# VDAC2.net
KiCad netlist of a schematic drawn in EAGLE
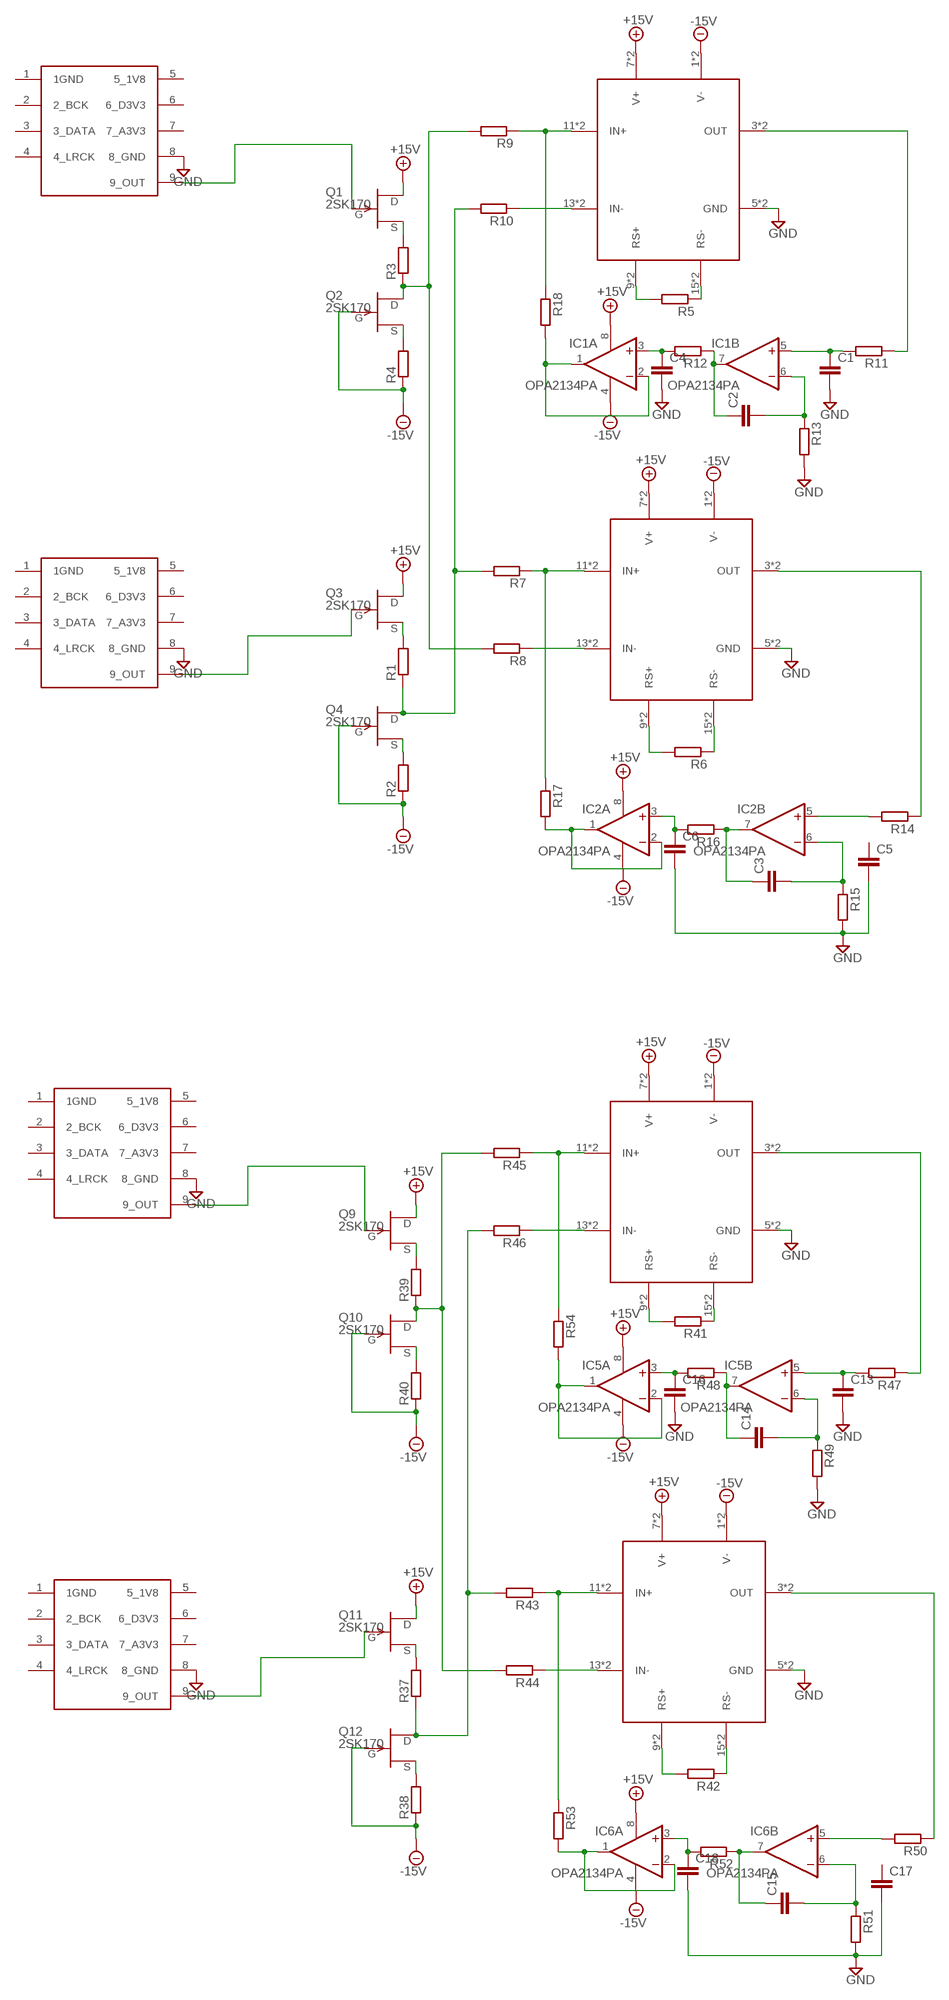
[diagram p0: schematic, sheet 1]

(export (version "E")
  (design (tool "Eeschema 10.0.6"))
  (components
    (comp (ref "C1")
      (value "C-EU050-050X075")
      (footprint "eagle-import:C050-050X075")
      (libsource (lib "eagle-import") (part "C-EU050-050X075"))
    )
    (comp (ref "C2")
      (value "C-EU050-035X075")
      (footprint "eagle-import:C050-035X075")
      (libsource (lib "eagle-import") (part "C-EU050-035X075"))
    )
    (comp (ref "C3")
      (value "C-EU050-035X075")
      (footprint "eagle-import:C050-035X075")
      (libsource (lib "eagle-import") (part "C-EU050-035X075"))
    )
    (comp (ref "C4")
      (value "C-EU050-035X075")
      (footprint "eagle-import:C050-035X075")
      (libsource (lib "eagle-import") (part "C-EU050-035X075"))
    )
    (comp (ref "C5")
      (value "C-EU050-050X075")
      (footprint "eagle-import:C050-050X075")
      (libsource (lib "eagle-import") (part "C-EU050-050X075"))
    )
    (comp (ref "C6")
      (value "C-EU050-035X075")
      (footprint "eagle-import:C050-035X075")
      (libsource (lib "eagle-import") (part "C-EU050-035X075"))
    )
    (comp (ref "C13")
      (value "C-EU050-050X075")
      (footprint "eagle-import:C050-050X075")
      (libsource (lib "eagle-import") (part "C-EU050-050X075"))
    )
    (comp (ref "C14")
      (value "C-EU050-035X075")
      (footprint "eagle-import:C050-035X075")
      (libsource (lib "eagle-import") (part "C-EU050-035X075"))
    )
    (comp (ref "C15")
      (value "C-EU050-035X075")
      (footprint "eagle-import:C050-035X075")
      (libsource (lib "eagle-import") (part "C-EU050-035X075"))
    )
    (comp (ref "C16")
      (value "C-EU050-035X075")
      (footprint "eagle-import:C050-035X075")
      (libsource (lib "eagle-import") (part "C-EU050-035X075"))
    )
    (comp (ref "C17")
      (value "C-EU050-050X075")
      (footprint "eagle-import:C050-050X075")
      (libsource (lib "eagle-import") (part "C-EU050-050X075"))
    )
    (comp (ref "C18")
      (value "C-EU050-035X075")
      (footprint "eagle-import:C050-035X075")
      (libsource (lib "eagle-import") (part "C-EU050-035X075"))
    )
    (comp (ref "IC1")
      (value "OPA2134PA")
      (footprint "eagle-import:DIL08")
      (libsource (lib "eagle-import") (part "OPA2PA134"))
    )
    (comp (ref "IC2")
      (value "OPA2134PA")
      (footprint "eagle-import:DIL08")
      (libsource (lib "eagle-import") (part "OPA2PA134"))
    )
    (comp (ref "IC5")
      (value "OPA2134PA")
      (footprint "eagle-import:DIL08")
      (libsource (lib "eagle-import") (part "OPA2PA134"))
    )
    (comp (ref "IC6")
      (value "OPA2134PA")
      (footprint "eagle-import:DIL08")
      (libsource (lib "eagle-import") (part "OPA2PA134"))
    )
    (comp (ref "Q1")
      (value "2SK170")
      (footprint "eagle-import:TO92-")
      (libsource (lib "eagle-import") (part "2SK170"))
    )
    (comp (ref "Q2")
      (value "2SK170")
      (footprint "eagle-import:TO92-")
      (libsource (lib "eagle-import") (part "2SK170"))
    )
    (comp (ref "Q3")
      (value "2SK170")
      (footprint "eagle-import:TO92-")
      (libsource (lib "eagle-import") (part "2SK170"))
    )
    (comp (ref "Q4")
      (value "2SK170")
      (footprint "eagle-import:TO92-")
      (libsource (lib "eagle-import") (part "2SK170"))
    )
    (comp (ref "Q9")
      (value "2SK170")
      (footprint "eagle-import:TO92-")
      (libsource (lib "eagle-import") (part "2SK170"))
    )
    (comp (ref "Q10")
      (value "2SK170")
      (footprint "eagle-import:TO92-")
      (libsource (lib "eagle-import") (part "2SK170"))
    )
    (comp (ref "Q11")
      (value "2SK170")
      (footprint "eagle-import:TO92-")
      (libsource (lib "eagle-import") (part "2SK170"))
    )
    (comp (ref "Q12")
      (value "2SK170")
      (footprint "eagle-import:TO92-")
      (libsource (lib "eagle-import") (part "2SK170"))
    )
    (comp (ref "R1")
      (value "R-EU_0309/10")
      (footprint "eagle-import:0309_10")
      (libsource (lib "eagle-import") (part "R-EU_0309/10"))
    )
    (comp (ref "R2")
      (value "R-EU_0309/10")
      (footprint "eagle-import:0309_10")
      (libsource (lib "eagle-import") (part "R-EU_0309/10"))
    )
    (comp (ref "R3")
      (value "R-EU_0309/10")
      (footprint "eagle-import:0309_10")
      (libsource (lib "eagle-import") (part "R-EU_0309/10"))
    )
    (comp (ref "R4")
      (value "R-EU_0309/10")
      (footprint "eagle-import:0309_10")
      (libsource (lib "eagle-import") (part "R-EU_0309/10"))
    )
    (comp (ref "R5")
      (value "R-EU_0309/10")
      (footprint "eagle-import:0309_10")
      (libsource (lib "eagle-import") (part "R-EU_0309/10"))
    )
    (comp (ref "R6")
      (value "R-EU_0309/10")
      (footprint "eagle-import:0309_10")
      (libsource (lib "eagle-import") (part "R-EU_0309/10"))
    )
    (comp (ref "R7")
      (value "R-EU_0309/10")
      (footprint "eagle-import:0309_10")
      (libsource (lib "eagle-import") (part "R-EU_0309/10"))
    )
    (comp (ref "R8")
      (value "R-EU_0309/10")
      (footprint "eagle-import:0309_10")
      (libsource (lib "eagle-import") (part "R-EU_0309/10"))
    )
    (comp (ref "R9")
      (value "R-EU_0309/10")
      (footprint "eagle-import:0309_10")
      (libsource (lib "eagle-import") (part "R-EU_0309/10"))
    )
    (comp (ref "R10")
      (value "R-EU_0309/10")
      (footprint "eagle-import:0309_10")
      (libsource (lib "eagle-import") (part "R-EU_0309/10"))
    )
    (comp (ref "R11")
      (value "R-EU_0309/10")
      (footprint "eagle-import:0309_10")
      (libsource (lib "eagle-import") (part "R-EU_0309/10"))
    )
    (comp (ref "R12")
      (value "R-EU_0309/10")
      (footprint "eagle-import:0309_10")
      (libsource (lib "eagle-import") (part "R-EU_0309/10"))
    )
    (comp (ref "R13")
      (value "R-EU_0309/10")
      (footprint "eagle-import:0309_10")
      (libsource (lib "eagle-import") (part "R-EU_0309/10"))
    )
    (comp (ref "R14")
      (value "R-EU_0309/10")
      (footprint "eagle-import:0309_10")
      (libsource (lib "eagle-import") (part "R-EU_0309/10"))
    )
    (comp (ref "R15")
      (value "R-EU_0309/10")
      (footprint "eagle-import:0309_10")
      (libsource (lib "eagle-import") (part "R-EU_0309/10"))
    )
    (comp (ref "R16")
      (value "R-EU_0309/10")
      (footprint "eagle-import:0309_10")
      (libsource (lib "eagle-import") (part "R-EU_0309/10"))
    )
    (comp (ref "R17")
      (value "R-EU_0309/10")
      (footprint "eagle-import:0309_10")
      (libsource (lib "eagle-import") (part "R-EU_0309/10"))
    )
    (comp (ref "R18")
      (value "R-EU_0309/10")
      (footprint "eagle-import:0309_10")
      (libsource (lib "eagle-import") (part "R-EU_0309/10"))
    )
    (comp (ref "R37")
      (value "R-EU_0309/10")
      (footprint "eagle-import:0309_10")
      (libsource (lib "eagle-import") (part "R-EU_0309/10"))
    )
    (comp (ref "R38")
      (value "R-EU_0309/10")
      (footprint "eagle-import:0309_10")
      (libsource (lib "eagle-import") (part "R-EU_0309/10"))
    )
    (comp (ref "R39")
      (value "R-EU_0309/10")
      (footprint "eagle-import:0309_10")
      (libsource (lib "eagle-import") (part "R-EU_0309/10"))
    )
    (comp (ref "R40")
      (value "R-EU_0309/10")
      (footprint "eagle-import:0309_10")
      (libsource (lib "eagle-import") (part "R-EU_0309/10"))
    )
    (comp (ref "R41")
      (value "R-EU_0309/10")
      (footprint "eagle-import:0309_10")
      (libsource (lib "eagle-import") (part "R-EU_0309/10"))
    )
    (comp (ref "R42")
      (value "R-EU_0309/10")
      (footprint "eagle-import:0309_10")
      (libsource (lib "eagle-import") (part "R-EU_0309/10"))
    )
    (comp (ref "R43")
      (value "R-EU_0309/10")
      (footprint "eagle-import:0309_10")
      (libsource (lib "eagle-import") (part "R-EU_0309/10"))
    )
    (comp (ref "R44")
      (value "R-EU_0309/10")
      (footprint "eagle-import:0309_10")
      (libsource (lib "eagle-import") (part "R-EU_0309/10"))
    )
    (comp (ref "R45")
      (value "R-EU_0309/10")
      (footprint "eagle-import:0309_10")
      (libsource (lib "eagle-import") (part "R-EU_0309/10"))
    )
    (comp (ref "R46")
      (value "R-EU_0309/10")
      (footprint "eagle-import:0309_10")
      (libsource (lib "eagle-import") (part "R-EU_0309/10"))
    )
    (comp (ref "R47")
      (value "R-EU_0309/10")
      (footprint "eagle-import:0309_10")
      (libsource (lib "eagle-import") (part "R-EU_0309/10"))
    )
    (comp (ref "R48")
      (value "R-EU_0309/10")
      (footprint "eagle-import:0309_10")
      (libsource (lib "eagle-import") (part "R-EU_0309/10"))
    )
    (comp (ref "R49")
      (value "R-EU_0309/10")
      (footprint "eagle-import:0309_10")
      (libsource (lib "eagle-import") (part "R-EU_0309/10"))
    )
    (comp (ref "R50")
      (value "R-EU_0309/10")
      (footprint "eagle-import:0309_10")
      (libsource (lib "eagle-import") (part "R-EU_0309/10"))
    )
    (comp (ref "R51")
      (value "R-EU_0309/10")
      (footprint "eagle-import:0309_10")
      (libsource (lib "eagle-import") (part "R-EU_0309/10"))
    )
    (comp (ref "R52")
      (value "R-EU_0309/10")
      (footprint "eagle-import:0309_10")
      (libsource (lib "eagle-import") (part "R-EU_0309/10"))
    )
    (comp (ref "R53")
      (value "R-EU_0309/10")
      (footprint "eagle-import:0309_10")
      (libsource (lib "eagle-import") (part "R-EU_0309/10"))
    )
    (comp (ref "R54")
      (value "R-EU_0309/10")
      (footprint "eagle-import:0309_10")
      (libsource (lib "eagle-import") (part "R-EU_0309/10"))
    )
    (comp (ref "U$1")
      (value "7130MOD")
      (footprint "eagle-import:7130MOD")
      (libsource (lib "eagle-import") (part "7130MOD"))
    )
    (comp (ref "U$2")
      (value "7130MOD")
      (footprint "eagle-import:7130MOD")
      (libsource (lib "eagle-import") (part "7130MOD"))
    )
    (comp (ref "U$5")
      (value "R2R")
      (footprint "eagle-import:R2R")
      (libsource (lib "eagle-import") (part "R2R"))
    )
    (comp (ref "U$6")
      (value "R2R")
      (footprint "eagle-import:R2R")
      (libsource (lib "eagle-import") (part "R2R"))
    )
    (comp (ref "U$9")
      (value "R2R")
      (footprint "eagle-import:R2R")
      (libsource (lib "eagle-import") (part "R2R"))
    )
    (comp (ref "U$10")
      (value "R2R")
      (footprint "eagle-import:R2R")
      (libsource (lib "eagle-import") (part "R2R"))
    )
    (comp (ref "U$11")
      (value "7130MOD")
      (footprint "eagle-import:7130MOD")
      (libsource (lib "eagle-import") (part "7130MOD"))
    )
    (comp (ref "U$12")
      (value "7130MOD")
      (footprint "eagle-import:7130MOD")
      (libsource (lib "eagle-import") (part "7130MOD"))
    )
  )
  (nets
    (net (code "1") (name "+15V") (class "Default")
      (node (ref "IC1") (pin "8") (pinfunction "V+_8") (pintype "power_in"))
      (node (ref "IC2") (pin "8") (pinfunction "V+_8") (pintype "power_in"))
      (node (ref "IC5") (pin "8") (pinfunction "V+_8") (pintype "power_in"))
      (node (ref "IC6") (pin "8") (pinfunction "V+_8") (pintype "power_in"))
      (node (ref "Q1") (pin "1") (pinfunction "D_1") (pintype "passive"))
      (node (ref "Q11") (pin "1") (pinfunction "D_1") (pintype "passive"))
      (node (ref "Q3") (pin "1") (pinfunction "D_1") (pintype "passive"))
      (node (ref "Q9") (pin "1") (pinfunction "D_1") (pintype "passive"))
      (node (ref "U$1") (pin "7") (pinfunction "V+_7") (pintype "bidirectional"))
      (node (ref "U$1") (pin "8") (pinfunction "V+_8") (pintype "bidirectional"))
      (node (ref "U$11") (pin "7") (pinfunction "V+_7") (pintype "bidirectional"))
      (node (ref "U$11") (pin "8") (pinfunction "V+_8") (pintype "bidirectional"))
      (node (ref "U$12") (pin "7") (pinfunction "V+_7") (pintype "bidirectional"))
      (node (ref "U$12") (pin "8") (pinfunction "V+_8") (pintype "bidirectional"))
      (node (ref "U$2") (pin "7") (pinfunction "V+_7") (pintype "bidirectional"))
      (node (ref "U$2") (pin "8") (pinfunction "V+_8") (pintype "bidirectional"))
    )
    (net (code "2") (name "-15V") (class "Default")
      (node (ref "IC1") (pin "4") (pinfunction "V-_4") (pintype "power_in"))
      (node (ref "IC2") (pin "4") (pinfunction "V-_4") (pintype "power_in"))
      (node (ref "IC5") (pin "4") (pinfunction "V-_4") (pintype "power_in"))
      (node (ref "IC6") (pin "4") (pinfunction "V-_4") (pintype "power_in"))
      (node (ref "Q10") (pin "2") (pinfunction "G_2") (pintype "passive"))
      (node (ref "Q12") (pin "2") (pinfunction "G_2") (pintype "passive"))
      (node (ref "Q2") (pin "2") (pinfunction "G_2") (pintype "passive"))
      (node (ref "Q4") (pin "2") (pinfunction "G_2") (pintype "passive"))
      (node (ref "R2") (pin "1") (pinfunction "1_1") (pintype "passive"))
      (node (ref "R38") (pin "1") (pinfunction "1_1") (pintype "passive"))
      (node (ref "R4") (pin "1") (pinfunction "1_1") (pintype "passive"))
      (node (ref "R40") (pin "1") (pinfunction "1_1") (pintype "passive"))
      (node (ref "U$1") (pin "1") (pinfunction "V-_1") (pintype "bidirectional"))
      (node (ref "U$1") (pin "2") (pinfunction "V-_2") (pintype "bidirectional"))
      (node (ref "U$11") (pin "1") (pinfunction "V-_1") (pintype "bidirectional"))
      (node (ref "U$11") (pin "2") (pinfunction "V-_2") (pintype "bidirectional"))
      (node (ref "U$12") (pin "1") (pinfunction "V-_1") (pintype "bidirectional"))
      (node (ref "U$12") (pin "2") (pinfunction "V-_2") (pintype "bidirectional"))
      (node (ref "U$2") (pin "1") (pinfunction "V-_1") (pintype "bidirectional"))
      (node (ref "U$2") (pin "2") (pinfunction "V-_2") (pintype "bidirectional"))
    )
    (net (code "3") (name "GND") (class "Default")
      (node (ref "C1") (pin "2") (pinfunction "2_2") (pintype "passive"))
      (node (ref "C13") (pin "2") (pinfunction "2_2") (pintype "passive"))
      (node (ref "C16") (pin "2") (pinfunction "2_2") (pintype "passive"))
      (node (ref "C17") (pin "2") (pinfunction "2_2") (pintype "passive"))
      (node (ref "C18") (pin "2") (pinfunction "2_2") (pintype "passive"))
      (node (ref "C4") (pin "2") (pinfunction "2_2") (pintype "passive"))
      (node (ref "C5") (pin "2") (pinfunction "2_2") (pintype "passive"))
      (node (ref "C6") (pin "2") (pinfunction "2_2") (pintype "passive"))
      (node (ref "R13") (pin "2") (pinfunction "2_2") (pintype "passive"))
      (node (ref "R15") (pin "2") (pinfunction "2_2") (pintype "passive"))
      (node (ref "R49") (pin "2") (pinfunction "2_2") (pintype "passive"))
      (node (ref "R51") (pin "2") (pinfunction "2_2") (pintype "passive"))
      (node (ref "U$1") (pin "5") (pinfunction "GND_5") (pintype "bidirectional"))
      (node (ref "U$1") (pin "6") (pinfunction "GND_6") (pintype "bidirectional"))
      (node (ref "U$10") (pin "8") (pinfunction "8_GND_8") (pintype "bidirectional"))
      (node (ref "U$11") (pin "5") (pinfunction "GND_5") (pintype "bidirectional"))
      (node (ref "U$11") (pin "6") (pinfunction "GND_6") (pintype "bidirectional"))
      (node (ref "U$12") (pin "5") (pinfunction "GND_5") (pintype "bidirectional"))
      (node (ref "U$12") (pin "6") (pinfunction "GND_6") (pintype "bidirectional"))
      (node (ref "U$2") (pin "5") (pinfunction "GND_5") (pintype "bidirectional"))
      (node (ref "U$2") (pin "6") (pinfunction "GND_6") (pintype "bidirectional"))
      (node (ref "U$5") (pin "8") (pinfunction "8_GND_8") (pintype "bidirectional"))
      (node (ref "U$6") (pin "8") (pinfunction "8_GND_8") (pintype "bidirectional"))
      (node (ref "U$9") (pin "8") (pinfunction "8_GND_8") (pintype "bidirectional"))
    )
    (net (code "4") (name "Net-(IC1A-+IN)") (class "Default")
      (node (ref "C4") (pin "1") (pinfunction "1_1") (pintype "passive"))
      (node (ref "IC1") (pin "3") (pinfunction "+IN_3") (pintype "input"))
      (node (ref "R12") (pin "2") (pinfunction "2_2") (pintype "passive"))
    )
    (net (code "5") (name "Net-(IC1A--IN)") (class "Default")
      (node (ref "IC1") (pin "1") (pinfunction "OUT_1") (pintype "output"))
      (node (ref "IC1") (pin "2") (pinfunction "-IN_2") (pintype "input"))
      (node (ref "R18") (pin "2") (pinfunction "2_2") (pintype "passive"))
    )
    (net (code "6") (name "Net-(IC1B-+IN)") (class "Default")
      (node (ref "C1") (pin "1") (pinfunction "1_1") (pintype "passive"))
      (node (ref "IC1") (pin "5") (pinfunction "+IN_5") (pintype "input"))
      (node (ref "R11") (pin "2") (pinfunction "2_2") (pintype "passive"))
    )
    (net (code "7") (name "Net-(IC1B--IN)") (class "Default")
      (node (ref "C2") (pin "2") (pinfunction "2_2") (pintype "passive"))
      (node (ref "IC1") (pin "6") (pinfunction "-IN_6") (pintype "input"))
      (node (ref "R13") (pin "1") (pinfunction "1_1") (pintype "passive"))
    )
    (net (code "8") (name "Net-(IC1B-OUT)") (class "Default")
      (node (ref "C2") (pin "1") (pinfunction "1_1") (pintype "passive"))
      (node (ref "IC1") (pin "7") (pinfunction "OUT_7") (pintype "output"))
      (node (ref "R12") (pin "1") (pinfunction "1_1") (pintype "passive"))
    )
    (net (code "9") (name "Net-(IC2A-+IN)") (class "Default")
      (node (ref "C6") (pin "1") (pinfunction "1_1") (pintype "passive"))
      (node (ref "IC2") (pin "3") (pinfunction "+IN_3") (pintype "input"))
      (node (ref "R16") (pin "2") (pinfunction "2_2") (pintype "passive"))
    )
    (net (code "10") (name "Net-(IC2A--IN)") (class "Default")
      (node (ref "IC2") (pin "1") (pinfunction "OUT_1") (pintype "output"))
      (node (ref "IC2") (pin "2") (pinfunction "-IN_2") (pintype "input"))
      (node (ref "R17") (pin "2") (pinfunction "2_2") (pintype "passive"))
    )
    (net (code "11") (name "Net-(IC2B-+IN)") (class "Default")
      (node (ref "IC2") (pin "5") (pinfunction "+IN_5") (pintype "input"))
      (node (ref "R14") (pin "2") (pinfunction "2_2") (pintype "passive"))
    )
    (net (code "12") (name "Net-(IC2B--IN)") (class "Default")
      (node (ref "C3") (pin "2") (pinfunction "2_2") (pintype "passive"))
      (node (ref "IC2") (pin "6") (pinfunction "-IN_6") (pintype "input"))
      (node (ref "R15") (pin "1") (pinfunction "1_1") (pintype "passive"))
    )
    (net (code "13") (name "Net-(IC2B-OUT)") (class "Default")
      (node (ref "C3") (pin "1") (pinfunction "1_1") (pintype "passive"))
      (node (ref "IC2") (pin "7") (pinfunction "OUT_7") (pintype "output"))
      (node (ref "R16") (pin "1") (pinfunction "1_1") (pintype "passive"))
    )
    (net (code "14") (name "Net-(IC5A-+IN)") (class "Default")
      (node (ref "C16") (pin "1") (pinfunction "1_1") (pintype "passive"))
      (node (ref "IC5") (pin "3") (pinfunction "+IN_3") (pintype "input"))
      (node (ref "R48") (pin "2") (pinfunction "2_2") (pintype "passive"))
    )
    (net (code "15") (name "Net-(IC5A--IN)") (class "Default")
      (node (ref "IC5") (pin "1") (pinfunction "OUT_1") (pintype "output"))
      (node (ref "IC5") (pin "2") (pinfunction "-IN_2") (pintype "input"))
      (node (ref "R54") (pin "2") (pinfunction "2_2") (pintype "passive"))
    )
    (net (code "16") (name "Net-(IC5B-+IN)") (class "Default")
      (node (ref "C13") (pin "1") (pinfunction "1_1") (pintype "passive"))
      (node (ref "IC5") (pin "5") (pinfunction "+IN_5") (pintype "input"))
      (node (ref "R47") (pin "2") (pinfunction "2_2") (pintype "passive"))
    )
    (net (code "17") (name "Net-(IC5B--IN)") (class "Default")
      (node (ref "C14") (pin "2") (pinfunction "2_2") (pintype "passive"))
      (node (ref "IC5") (pin "6") (pinfunction "-IN_6") (pintype "input"))
      (node (ref "R49") (pin "1") (pinfunction "1_1") (pintype "passive"))
    )
    (net (code "18") (name "Net-(IC5B-OUT)") (class "Default")
      (node (ref "C14") (pin "1") (pinfunction "1_1") (pintype "passive"))
      (node (ref "IC5") (pin "7") (pinfunction "OUT_7") (pintype "output"))
      (node (ref "R48") (pin "1") (pinfunction "1_1") (pintype "passive"))
    )
    (net (code "19") (name "Net-(IC6A-+IN)") (class "Default")
      (node (ref "C18") (pin "1") (pinfunction "1_1") (pintype "passive"))
      (node (ref "IC6") (pin "3") (pinfunction "+IN_3") (pintype "input"))
      (node (ref "R52") (pin "2") (pinfunction "2_2") (pintype "passive"))
    )
    (net (code "20") (name "Net-(IC6A--IN)") (class "Default")
      (node (ref "IC6") (pin "1") (pinfunction "OUT_1") (pintype "output"))
      (node (ref "IC6") (pin "2") (pinfunction "-IN_2") (pintype "input"))
      (node (ref "R53") (pin "2") (pinfunction "2_2") (pintype "passive"))
    )
    (net (code "21") (name "Net-(IC6B-+IN)") (class "Default")
      (node (ref "IC6") (pin "5") (pinfunction "+IN_5") (pintype "input"))
      (node (ref "R50") (pin "2") (pinfunction "2_2") (pintype "passive"))
    )
    (net (code "22") (name "Net-(IC6B--IN)") (class "Default")
      (node (ref "C15") (pin "2") (pinfunction "2_2") (pintype "passive"))
      (node (ref "IC6") (pin "6") (pinfunction "-IN_6") (pintype "input"))
      (node (ref "R51") (pin "1") (pinfunction "1_1") (pintype "passive"))
    )
    (net (code "23") (name "Net-(IC6B-OUT)") (class "Default")
      (node (ref "C15") (pin "1") (pinfunction "1_1") (pintype "passive"))
      (node (ref "IC6") (pin "7") (pinfunction "OUT_7") (pintype "output"))
      (node (ref "R52") (pin "1") (pinfunction "1_1") (pintype "passive"))
    )
    (net (code "24") (name "Net-(Q1-G)") (class "Default")
      (node (ref "Q1") (pin "2") (pinfunction "G_2") (pintype "passive"))
      (node (ref "U$5") (pin "9") (pinfunction "9_OUT_9") (pintype "bidirectional"))
    )
    (net (code "25") (name "Net-(Q1-S)") (class "Default")
      (node (ref "Q1") (pin "3") (pinfunction "S_3") (pintype "passive"))
      (node (ref "R3") (pin "2") (pinfunction "2_2") (pintype "passive"))
    )
    (net (code "26") (name "Net-(Q2-D)") (class "Default")
      (node (ref "Q2") (pin "1") (pinfunction "D_1") (pintype "passive"))
      (node (ref "R3") (pin "1") (pinfunction "1_1") (pintype "passive"))
      (node (ref "R8") (pin "2") (pinfunction "2_2") (pintype "passive"))
      (node (ref "R9") (pin "2") (pinfunction "2_2") (pintype "passive"))
    )
    (net (code "27") (name "Net-(Q2-S)") (class "Default")
      (node (ref "Q2") (pin "3") (pinfunction "S_3") (pintype "passive"))
      (node (ref "R4") (pin "2") (pinfunction "2_2") (pintype "passive"))
    )
    (net (code "28") (name "Net-(Q3-G)") (class "Default")
      (node (ref "Q3") (pin "2") (pinfunction "G_2") (pintype "passive"))
      (node (ref "U$6") (pin "9") (pinfunction "9_OUT_9") (pintype "bidirectional"))
    )
    (net (code "29") (name "Net-(Q3-S)") (class "Default")
      (node (ref "Q3") (pin "3") (pinfunction "S_3") (pintype "passive"))
      (node (ref "R1") (pin "2") (pinfunction "2_2") (pintype "passive"))
    )
    (net (code "30") (name "Net-(Q4-D)") (class "Default")
      (node (ref "Q4") (pin "1") (pinfunction "D_1") (pintype "passive"))
      (node (ref "R1") (pin "1") (pinfunction "1_1") (pintype "passive"))
      (node (ref "R10") (pin "2") (pinfunction "2_2") (pintype "passive"))
      (node (ref "R7") (pin "2") (pinfunction "2_2") (pintype "passive"))
    )
    (net (code "31") (name "Net-(Q4-S)") (class "Default")
      (node (ref "Q4") (pin "3") (pinfunction "S_3") (pintype "passive"))
      (node (ref "R2") (pin "2") (pinfunction "2_2") (pintype "passive"))
    )
    (net (code "32") (name "Net-(Q9-G)") (class "Default")
      (node (ref "Q9") (pin "2") (pinfunction "G_2") (pintype "passive"))
      (node (ref "U$9") (pin "9") (pinfunction "9_OUT_9") (pintype "bidirectional"))
    )
    (net (code "33") (name "Net-(Q9-S)") (class "Default")
      (node (ref "Q9") (pin "3") (pinfunction "S_3") (pintype "passive"))
      (node (ref "R39") (pin "2") (pinfunction "2_2") (pintype "passive"))
    )
    (net (code "34") (name "Net-(Q10-D)") (class "Default")
      (node (ref "Q10") (pin "1") (pinfunction "D_1") (pintype "passive"))
      (node (ref "R39") (pin "1") (pinfunction "1_1") (pintype "passive"))
      (node (ref "R44") (pin "2") (pinfunction "2_2") (pintype "passive"))
      (node (ref "R45") (pin "2") (pinfunction "2_2") (pintype "passive"))
    )
    (net (code "35") (name "Net-(Q10-S)") (class "Default")
      (node (ref "Q10") (pin "3") (pinfunction "S_3") (pintype "passive"))
      (node (ref "R40") (pin "2") (pinfunction "2_2") (pintype "passive"))
    )
    (net (code "36") (name "Net-(Q11-G)") (class "Default")
      (node (ref "Q11") (pin "2") (pinfunction "G_2") (pintype "passive"))
      (node (ref "U$10") (pin "9") (pinfunction "9_OUT_9") (pintype "bidirectional"))
    )
    (net (code "37") (name "Net-(Q11-S)") (class "Default")
      (node (ref "Q11") (pin "3") (pinfunction "S_3") (pintype "passive"))
      (node (ref "R37") (pin "2") (pinfunction "2_2") (pintype "passive"))
    )
    (net (code "38") (name "Net-(Q12-D)") (class "Default")
      (node (ref "Q12") (pin "1") (pinfunction "D_1") (pintype "passive"))
      (node (ref "R37") (pin "1") (pinfunction "1_1") (pintype "passive"))
      (node (ref "R43") (pin "2") (pinfunction "2_2") (pintype "passive"))
      (node (ref "R46") (pin "2") (pinfunction "2_2") (pintype "passive"))
    )
    (net (code "39") (name "Net-(Q12-S)") (class "Default")
      (node (ref "Q12") (pin "3") (pinfunction "S_3") (pintype "passive"))
      (node (ref "R38") (pin "2") (pinfunction "2_2") (pintype "passive"))
    )
    (net (code "40") (name "Net-(R5-Pad1)") (class "Default")
      (node (ref "R5") (pin "1") (pinfunction "1_1") (pintype "passive"))
      (node (ref "U$2") (pin "15") (pinfunction "RS-_15") (pintype "bidirectional"))
      (node (ref "U$2") (pin "16") (pinfunction "RS-_16") (pintype "bidirectional"))
    )
    (net (code "41") (name "Net-(R5-Pad2)") (class "Default")
      (node (ref "R5") (pin "2") (pinfunction "2_2") (pintype "passive"))
      (node (ref "U$2") (pin "10") (pinfunction "RS+_10") (pintype "bidirectional"))
      (node (ref "U$2") (pin "9") (pinfunction "RS+_9") (pintype "bidirectional"))
    )
    (net (code "42") (name "Net-(R6-Pad1)") (class "Default")
      (node (ref "R6") (pin "1") (pinfunction "1_1") (pintype "passive"))
      (node (ref "U$1") (pin "15") (pinfunction "RS-_15") (pintype "bidirectional"))
      (node (ref "U$1") (pin "16") (pinfunction "RS-_16") (pintype "bidirectional"))
    )
    (net (code "43") (name "Net-(R6-Pad2)") (class "Default")
      (node (ref "R6") (pin "2") (pinfunction "2_2") (pintype "passive"))
      (node (ref "U$1") (pin "10") (pinfunction "RS+_10") (pintype "bidirectional"))
      (node (ref "U$1") (pin "9") (pinfunction "RS+_9") (pintype "bidirectional"))
    )
    (net (code "44") (name "Net-(R8-Pad1)") (class "Default")
      (node (ref "R8") (pin "1") (pinfunction "1_1") (pintype "passive"))
      (node (ref "U$1") (pin "13") (pinfunction "IN-_13") (pintype "bidirectional"))
      (node (ref "U$1") (pin "14") (pinfunction "IN-_14") (pintype "bidirectional"))
    )
    (net (code "45") (name "Net-(R10-Pad1)") (class "Default")
      (node (ref "R10") (pin "1") (pinfunction "1_1") (pintype "passive"))
      (node (ref "U$2") (pin "13") (pinfunction "IN-_13") (pintype "bidirectional"))
      (node (ref "U$2") (pin "14") (pinfunction "IN-_14") (pintype "bidirectional"))
    )
    (net (code "46") (name "Net-(R11-Pad1)") (class "Default")
      (node (ref "R11") (pin "1") (pinfunction "1_1") (pintype "passive"))
      (node (ref "U$2") (pin "3") (pinfunction "OUT_3") (pintype "bidirectional"))
      (node (ref "U$2") (pin "4") (pinfunction "OUT_4") (pintype "bidirectional"))
    )
    (net (code "47") (name "Net-(R14-Pad1)") (class "Default")
      (node (ref "R14") (pin "1") (pinfunction "1_1") (pintype "passive"))
      (node (ref "U$1") (pin "3") (pinfunction "OUT_3") (pintype "bidirectional"))
      (node (ref "U$1") (pin "4") (pinfunction "OUT_4") (pintype "bidirectional"))
    )
    (net (code "48") (name "Net-(R17-Pad1)") (class "Default")
      (node (ref "R17") (pin "1") (pinfunction "1_1") (pintype "passive"))
      (node (ref "R7") (pin "1") (pinfunction "1_1") (pintype "passive"))
      (node (ref "U$1") (pin "11") (pinfunction "IN+_11") (pintype "bidirectional"))
      (node (ref "U$1") (pin "12") (pinfunction "IN+_12") (pintype "bidirectional"))
    )
    (net (code "49") (name "Net-(R18-Pad1)") (class "Default")
      (node (ref "R18") (pin "1") (pinfunction "1_1") (pintype "passive"))
      (node (ref "R9") (pin "1") (pinfunction "1_1") (pintype "passive"))
      (node (ref "U$2") (pin "11") (pinfunction "IN+_11") (pintype "bidirectional"))
      (node (ref "U$2") (pin "12") (pinfunction "IN+_12") (pintype "bidirectional"))
    )
    (net (code "50") (name "Net-(R41-Pad1)") (class "Default")
      (node (ref "R41") (pin "1") (pinfunction "1_1") (pintype "passive"))
      (node (ref "U$12") (pin "15") (pinfunction "RS-_15") (pintype "bidirectional"))
      (node (ref "U$12") (pin "16") (pinfunction "RS-_16") (pintype "bidirectional"))
    )
    (net (code "51") (name "Net-(R41-Pad2)") (class "Default")
      (node (ref "R41") (pin "2") (pinfunction "2_2") (pintype "passive"))
      (node (ref "U$12") (pin "10") (pinfunction "RS+_10") (pintype "bidirectional"))
      (node (ref "U$12") (pin "9") (pinfunction "RS+_9") (pintype "bidirectional"))
    )
    (net (code "52") (name "Net-(R42-Pad1)") (class "Default")
      (node (ref "R42") (pin "1") (pinfunction "1_1") (pintype "passive"))
      (node (ref "U$11") (pin "15") (pinfunction "RS-_15") (pintype "bidirectional"))
      (node (ref "U$11") (pin "16") (pinfunction "RS-_16") (pintype "bidirectional"))
    )
    (net (code "53") (name "Net-(R42-Pad2)") (class "Default")
      (node (ref "R42") (pin "2") (pinfunction "2_2") (pintype "passive"))
      (node (ref "U$11") (pin "10") (pinfunction "RS+_10") (pintype "bidirectional"))
      (node (ref "U$11") (pin "9") (pinfunction "RS+_9") (pintype "bidirectional"))
    )
    (net (code "54") (name "Net-(R43-Pad1)") (class "Default")
      (node (ref "R43") (pin "1") (pinfunction "1_1") (pintype "passive"))
      (node (ref "R53") (pin "1") (pinfunction "1_1") (pintype "passive"))
      (node (ref "U$11") (pin "11") (pinfunction "IN+_11") (pintype "bidirectional"))
      (node (ref "U$11") (pin "12") (pinfunction "IN+_12") (pintype "bidirectional"))
    )
    (net (code "55") (name "Net-(R44-Pad1)") (class "Default")
      (node (ref "R44") (pin "1") (pinfunction "1_1") (pintype "passive"))
      (node (ref "U$11") (pin "13") (pinfunction "IN-_13") (pintype "bidirectional"))
      (node (ref "U$11") (pin "14") (pinfunction "IN-_14") (pintype "bidirectional"))
    )
    (net (code "56") (name "Net-(R45-Pad1)") (class "Default")
      (node (ref "R45") (pin "1") (pinfunction "1_1") (pintype "passive"))
      (node (ref "R54") (pin "1") (pinfunction "1_1") (pintype "passive"))
      (node (ref "U$12") (pin "11") (pinfunction "IN+_11") (pintype "bidirectional"))
      (node (ref "U$12") (pin "12") (pinfunction "IN+_12") (pintype "bidirectional"))
    )
    (net (code "57") (name "Net-(R46-Pad1)") (class "Default")
      (node (ref "R46") (pin "1") (pinfunction "1_1") (pintype "passive"))
      (node (ref "U$12") (pin "13") (pinfunction "IN-_13") (pintype "bidirectional"))
      (node (ref "U$12") (pin "14") (pinfunction "IN-_14") (pintype "bidirectional"))
    )
    (net (code "58") (name "Net-(R47-Pad1)") (class "Default")
      (node (ref "R47") (pin "1") (pinfunction "1_1") (pintype "passive"))
      (node (ref "U$12") (pin "3") (pinfunction "OUT_3") (pintype "bidirectional"))
      (node (ref "U$12") (pin "4") (pinfunction "OUT_4") (pintype "bidirectional"))
    )
    (net (code "59") (name "Net-(R50-Pad1)") (class "Default")
      (node (ref "R50") (pin "1") (pinfunction "1_1") (pintype "passive"))
      (node (ref "U$11") (pin "3") (pinfunction "OUT_3") (pintype "bidirectional"))
      (node (ref "U$11") (pin "4") (pinfunction "OUT_4") (pintype "bidirectional"))
    )
    (net (code "60") (name "unconnected-(C5-Pad1)") (class "Default")
      (node (ref "C5") (pin "1") (pinfunction "1_1") (pintype "passive"))
    )
    (net (code "61") (name "unconnected-(C17-Pad1)") (class "Default")
      (node (ref "C17") (pin "1") (pinfunction "1_1") (pintype "passive"))
    )
    (net (code "62") (name "unconnected-(U$5-1GND-Pad1)") (class "Default")
      (node (ref "U$5") (pin "1") (pinfunction "1GND_1") (pintype "bidirectional"))
    )
    (net (code "63") (name "unconnected-(U$5-2_BCK-Pad2)") (class "Default")
      (node (ref "U$5") (pin "2") (pinfunction "2_BCK_2") (pintype "bidirectional"))
    )
    (net (code "64") (name "unconnected-(U$5-3_DATA-Pad3)") (class "Default")
      (node (ref "U$5") (pin "3") (pinfunction "3_DATA_3") (pintype "bidirectional"))
    )
    (net (code "65") (name "unconnected-(U$5-4_LRCK-Pad4)") (class "Default")
      (node (ref "U$5") (pin "4") (pinfunction "4_LRCK_4") (pintype "bidirectional"))
    )
    (net (code "66") (name "unconnected-(U$5-5_1V8-Pad5)") (class "Default")
      (node (ref "U$5") (pin "5") (pinfunction "5_1V8_5") (pintype "bidirectional"))
    )
    (net (code "67") (name "unconnected-(U$5-6_D3V3-Pad6)") (class "Default")
      (node (ref "U$5") (pin "6") (pinfunction "6_D3V3_6") (pintype "bidirectional"))
    )
    (net (code "68") (name "unconnected-(U$5-7_A3V3-Pad7)") (class "Default")
      (node (ref "U$5") (pin "7") (pinfunction "7_A3V3_7") (pintype "bidirectional"))
    )
    (net (code "69") (name "unconnected-(U$6-1GND-Pad1)") (class "Default")
      (node (ref "U$6") (pin "1") (pinfunction "1GND_1") (pintype "bidirectional"))
    )
    (net (code "70") (name "unconnected-(U$6-2_BCK-Pad2)") (class "Default")
      (node (ref "U$6") (pin "2") (pinfunction "2_BCK_2") (pintype "bidirectional"))
    )
    (net (code "71") (name "unconnected-(U$6-3_DATA-Pad3)") (class "Default")
      (node (ref "U$6") (pin "3") (pinfunction "3_DATA_3") (pintype "bidirectional"))
    )
    (net (code "72") (name "unconnected-(U$6-4_LRCK-Pad4)") (class "Default")
      (node (ref "U$6") (pin "4") (pinfunction "4_LRCK_4") (pintype "bidirectional"))
    )
    (net (code "73") (name "unconnected-(U$6-5_1V8-Pad5)") (class "Default")
      (node (ref "U$6") (pin "5") (pinfunction "5_1V8_5") (pintype "bidirectional"))
    )
    (net (code "74") (name "unconnected-(U$6-6_D3V3-Pad6)") (class "Default")
      (node (ref "U$6") (pin "6") (pinfunction "6_D3V3_6") (pintype "bidirectional"))
    )
    (net (code "75") (name "unconnected-(U$6-7_A3V3-Pad7)") (class "Default")
      (node (ref "U$6") (pin "7") (pinfunction "7_A3V3_7") (pintype "bidirectional"))
    )
    (net (code "76") (name "unconnected-(U$9-1GND-Pad1)") (class "Default")
      (node (ref "U$9") (pin "1") (pinfunction "1GND_1") (pintype "bidirectional"))
    )
    (net (code "77") (name "unconnected-(U$9-2_BCK-Pad2)") (class "Default")
      (node (ref "U$9") (pin "2") (pinfunction "2_BCK_2") (pintype "bidirectional"))
    )
    (net (code "78") (name "unconnected-(U$9-3_DATA-Pad3)") (class "Default")
      (node (ref "U$9") (pin "3") (pinfunction "3_DATA_3") (pintype "bidirectional"))
    )
    (net (code "79") (name "unconnected-(U$9-4_LRCK-Pad4)") (class "Default")
      (node (ref "U$9") (pin "4") (pinfunction "4_LRCK_4") (pintype "bidirectional"))
    )
    (net (code "80") (name "unconnected-(U$9-5_1V8-Pad5)") (class "Default")
      (node (ref "U$9") (pin "5") (pinfunction "5_1V8_5") (pintype "bidirectional"))
    )
    (net (code "81") (name "unconnected-(U$9-6_D3V3-Pad6)") (class "Default")
      (node (ref "U$9") (pin "6") (pinfunction "6_D3V3_6") (pintype "bidirectional"))
    )
    (net (code "82") (name "unconnected-(U$9-7_A3V3-Pad7)") (class "Default")
      (node (ref "U$9") (pin "7") (pinfunction "7_A3V3_7") (pintype "bidirectional"))
    )
    (net (code "83") (name "unconnected-(U$10-1GND-Pad1)") (class "Default")
      (node (ref "U$10") (pin "1") (pinfunction "1GND_1") (pintype "bidirectional"))
    )
    (net (code "84") (name "unconnected-(U$10-2_BCK-Pad2)") (class "Default")
      (node (ref "U$10") (pin "2") (pinfunction "2_BCK_2") (pintype "bidirectional"))
    )
    (net (code "85") (name "unconnected-(U$10-3_DATA-Pad3)") (class "Default")
      (node (ref "U$10") (pin "3") (pinfunction "3_DATA_3") (pintype "bidirectional"))
    )
    (net (code "86") (name "unconnected-(U$10-4_LRCK-Pad4)") (class "Default")
      (node (ref "U$10") (pin "4") (pinfunction "4_LRCK_4") (pintype "bidirectional"))
    )
    (net (code "87") (name "unconnected-(U$10-5_1V8-Pad5)") (class "Default")
      (node (ref "U$10") (pin "5") (pinfunction "5_1V8_5") (pintype "bidirectional"))
    )
    (net (code "88") (name "unconnected-(U$10-6_D3V3-Pad6)") (class "Default")
      (node (ref "U$10") (pin "6") (pinfunction "6_D3V3_6") (pintype "bidirectional"))
    )
    (net (code "89") (name "unconnected-(U$10-7_A3V3-Pad7)") (class "Default")
      (node (ref "U$10") (pin "7") (pinfunction "7_A3V3_7") (pintype "bidirectional"))
    )
  )
)
